# Voltage_Regulator.net
KiCad netlist of a schematic drawn in Altium Designer
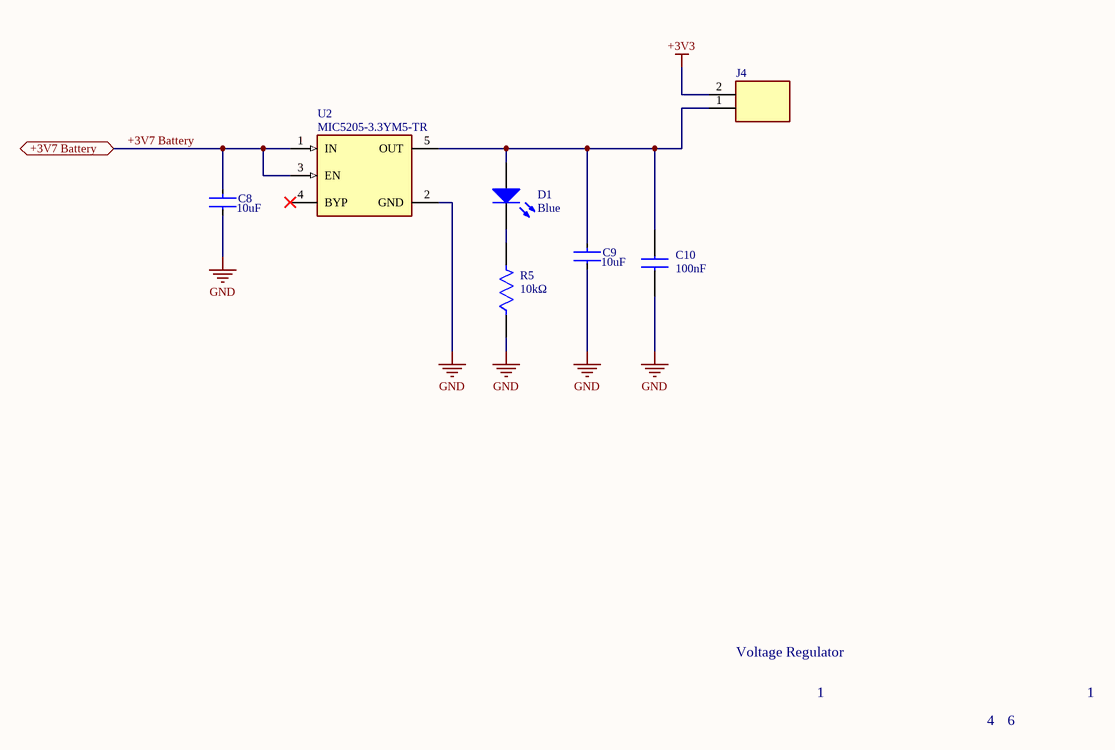
[diagram p0: Voltage Regulator.SchDoc]

(export (version "E")
  (design (tool "Eeschema 10.0.6"))
  (components
    (comp (ref "C8")
      (value "10uF")
      (footprint "FP-GCM21B-0_2-e0_2_0_7-MFG")
      (description "10 µF ±10% 25V Ceramic Capacitor X7S 0805 (2012 Metric)")
      (fields (field (name "Comment") "GCM21BC71E106KE36L"))
      (libsource (lib "Altium Content Vault") (part "11868f565c42a9108669ba33697ecf6"))
    )
    (comp (ref "C9")
      (value "10uF")
      (footprint "FP-GCM21B-0_2-e0_2_0_7-MFG")
      (description "10 µF ±10% 25V Ceramic Capacitor X7S 0805 (2012 Metric)")
      (fields (field (name "Comment") "GCM21BC71E106KE36L"))
      (libsource (lib "Altium Content Vault") (part "11868f565c42a9108669ba33697ecf6"))
    )
    (comp (ref "C10")
      (value "100nF")
      (footprint "SamacSys:CAPC2013X137N")
      (description "Capacitor")
      (fields
        (field (name "MANUFACTURER_PART_NUMBER") "0805B104K500NT")
        (field (name "MOUSER PART NUMBER") "767-0805B104K500NT")
      )
      (libsource (lib "*") (part "0805B104K500NT"))
    )
    (comp (ref "D1")
      (value "150120BS75000")
      (footprint "WL-SMCW_1206_150120xx75000")
      (fields (field (name "COLOR") "Blue"))
      (libsource (lib "Altium Content Vault") (part "LED_Blue_2A-1K"))
    )
    (comp (ref "J4")
      (value "87527-2")
      (footprint "SamacSys:HDRV2W66P0X254_1X2_467X244X1044P")
      (description "Power isolation jumper")
      (fields (field (name "MOUSER PART NUMBER") "571-875272"))
      (libsource (lib "*") (part "87527-2"))
    )
    (comp (ref "R5")
      (value "10kΩ")
      (footprint "FP-CR0805-IPC_A")
      (description "Thick Film Chip Resistors 0805 10kΩ 0.125W 1% 100ppm/°C")
      (fields (field (name "TOLERANCE") "1%") (field (name "Comment") "CR0805-FX-1002ELF"))
      (libsource (lib "Altium Content Vault") (part "1029c3af85768c4190bb7ad29bc67b5"))
    )
    (comp (ref "U2")
      (value "MIC5205-3.3YM5-TR")
      (footprint "FP-M5-MFG")
      (description "IC REG LINEAR 3.3V 150MA SOT23-5")
      (fields
        (field (name "MANUFACTURER") "Microchip")
        (field (name "OCTOPART") "https://octopart.com/mic5205-3.3ym5-tr-microchip-66802130")
      )
      (libsource (lib "Altium Content Vault") (part "b2bb7f462d557aec50a251fc6568b2e"))
    )
  )
  (nets
    (net (code "1") (name "+3V3") (class "Default")
      (node (ref "J4") (pin "2") (pinfunction "2_2") (pintype "passive"))
    )
    (net (code "2") (name "/+3V7 Battery") (class "Default")
      (node (ref "C8") (pin "1") (pinfunction "1_1") (pintype "passive"))
      (node (ref "U2") (pin "1") (pinfunction "IN_1") (pintype "input"))
      (node (ref "U2") (pin "3") (pinfunction "EN_3") (pintype "input"))
    )
    (net (code "3") (name "GND") (class "Default")
      (node (ref "C10") (pin "2") (pinfunction "2_2") (pintype "passive"))
      (node (ref "C8") (pin "2") (pinfunction "2_2") (pintype "passive"))
      (node (ref "C9") (pin "2") (pinfunction "2_2") (pintype "passive"))
      (node (ref "R5") (pin "1") (pinfunction "1_1") (pintype "passive"))
      (node (ref "U2") (pin "2") (pinfunction "GND_2") (pintype "power_in"))
    )
    (net (code "4") (name "Net-(D1-A)") (class "Default")
      (node (ref "C10") (pin "1") (pinfunction "1_1") (pintype "passive"))
      (node (ref "C9") (pin "1") (pinfunction "1_1") (pintype "passive"))
      (node (ref "D1") (pin "2") (pinfunction "A_2") (pintype "passive"))
      (node (ref "J4") (pin "1") (pinfunction "1_1") (pintype "passive"))
      (node (ref "U2") (pin "5") (pinfunction "OUT_5") (pintype "power_in"))
    )
    (net (code "5") (name "Net-(D1-K)") (class "Default")
      (node (ref "D1") (pin "1") (pinfunction "K_1") (pintype "passive"))
      (node (ref "R5") (pin "2") (pinfunction "2_2") (pintype "passive"))
    )
    (net (code "6") (name "unconnected-(U2-BYP-Pad4)") (class "Default")
      (node (ref "U2") (pin "4") (pinfunction "BYP_4") (pintype "passive+no_connect"))
    )
  )
)
